# Strain_Gauge_Amplifier.net
KiCad netlist of a schematic drawn in EAGLE
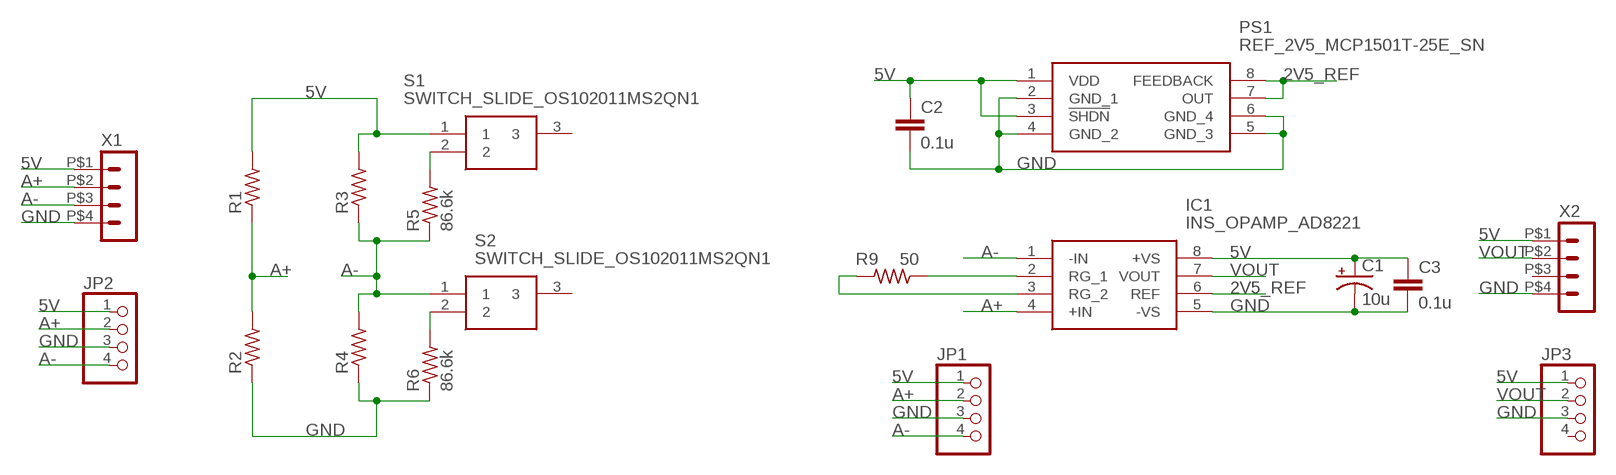
[diagram p0: schematic, sheet 1]

(export (version "E")
  (design (tool "Eeschema 10.0.6"))
  (components
    (comp (ref "C1")
      (value "10u")
      (footprint "eagle-import:E2-5")
      (libsource (lib "eagle-import") (part "CAP_THTE2-5"))
    )
    (comp (ref "C2")
      (value "0.1u")
      (footprint "eagle-import:C0603")
      (libsource (lib "eagle-import") (part "CAP_SMDC0603"))
    )
    (comp (ref "C3")
      (value "0.1u")
      (footprint "eagle-import:C0603")
      (libsource (lib "eagle-import") (part "CAP_SMDC0603"))
    )
    (comp (ref "IC1")
      (value "INS_OPAMP_AD8221")
      (footprint "eagle-import:SOP65P490X110-8N")
      (fields
        (field (name "ARROW_PART_NUMBER") "AD8221ARMZ-R7")
        (field (name "MOUSER_PART_NUMBER") "584-AD8221ARMZ-R7")
      )
      (libsource (lib "eagle-import") (part "INS_OPAMP_AD8221"))
    )
    (comp (ref "JP1")
      (value "PINHD-1X4")
      (footprint "eagle-import:1X04")
      (libsource (lib "eagle-import") (part "PINHD-1X4"))
    )
    (comp (ref "JP2")
      (value "PINHD-1X4")
      (footprint "eagle-import:1X04")
      (libsource (lib "eagle-import") (part "PINHD-1X4"))
    )
    (comp (ref "JP3")
      (value "PINHD-1X4")
      (footprint "eagle-import:1X04")
      (libsource (lib "eagle-import") (part "PINHD-1X4"))
    )
    (comp (ref "PS1")
      (value "REF_2V5_MCP1501T-25E_SN")
      (footprint "eagle-import:SOIC127P600X175-8N")
      (fields
        (field (name "ARROW_PART_NUMBER") "MCP1501T-25E/SN")
        (field (name "MOUSER_PART_NUMBER") "579-MCP1501T-25E/SN")
      )
      (libsource (lib "eagle-import") (part "REF_2V5_MCP1501T-25E_SN"))
    )
    (comp (ref "R1")
      (value "RES_SMDR1206")
      (footprint "eagle-import:R1206")
      (libsource (lib "eagle-import") (part "RES_SMDR1206"))
    )
    (comp (ref "R2")
      (value "RES_SMDR1206")
      (footprint "eagle-import:R1206")
      (libsource (lib "eagle-import") (part "RES_SMDR1206"))
    )
    (comp (ref "R3")
      (value "RES_SMDR1206")
      (footprint "eagle-import:R1206")
      (libsource (lib "eagle-import") (part "RES_SMDR1206"))
    )
    (comp (ref "R4")
      (value "RES_SMDR1206")
      (footprint "eagle-import:R1206")
      (libsource (lib "eagle-import") (part "RES_SMDR1206"))
    )
    (comp (ref "R5")
      (value "86.6k")
      (footprint "eagle-import:R0603")
      (libsource (lib "eagle-import") (part "RES_SMDR0603"))
    )
    (comp (ref "R6")
      (value "86.6k")
      (footprint "eagle-import:R0603")
      (libsource (lib "eagle-import") (part "RES_SMDR0603"))
    )
    (comp (ref "R9")
      (value "50")
      (footprint "eagle-import:R0603")
      (libsource (lib "eagle-import") (part "RES_SMDR0603"))
    )
    (comp (ref "S1")
      (value "SWITCH_SLIDE_OS102011MS2QN1")
      (footprint "eagle-import:OS102011MA1QN1")
      (fields
        (field (name "ARROW_PART_NUMBER") "OS102011MS2QN1")
        (field (name "MOUSER_PART_NUMBER") "611-OS102011MS2QN1")
      )
      (libsource (lib "eagle-import") (part "SWITCH_SLIDE_OS102011MS2QN1"))
    )
    (comp (ref "S2")
      (value "SWITCH_SLIDE_OS102011MS2QN1")
      (footprint "eagle-import:OS102011MA1QN1")
      (fields
        (field (name "ARROW_PART_NUMBER") "OS102011MS2QN1")
        (field (name "MOUSER_PART_NUMBER") "611-OS102011MS2QN1")
      )
      (libsource (lib "eagle-import") (part "SWITCH_SLIDE_OS102011MS2QN1"))
    )
    (comp (ref "X1")
      (value "HEADER_POS4_43045-0401")
      (footprint "eagle-import:43045-0400")
      (libsource (lib "eagle-import") (part "HEADER_POS4_?43045-0401"))
    )
    (comp (ref "X2")
      (value "HEADER_POS4_43045-0401")
      (footprint "eagle-import:43045-0400")
      (libsource (lib "eagle-import") (part "HEADER_POS4_?43045-0401"))
    )
  )
  (nets
    (net (code "1") (name "/2V5_REF") (class "Default")
      (node (ref "IC1") (pin "6") (pinfunction "REF_6") (pintype "bidirectional"))
      (node (ref "PS1") (pin "7") (pinfunction "OUT_7") (pintype "bidirectional"))
      (node (ref "PS1") (pin "8") (pinfunction "FEEDBACK_8") (pintype "bidirectional"))
    )
    (net (code "2") (name "/5V") (class "Default")
      (node (ref "C1") (pin "+") (pinfunction "+_+") (pintype "passive"))
      (node (ref "C2") (pin "1") (pinfunction "1_1") (pintype "passive"))
      (node (ref "C3") (pin "1") (pinfunction "1_1") (pintype "passive"))
      (node (ref "IC1") (pin "8") (pinfunction "+VS_8") (pintype "bidirectional"))
      (node (ref "JP1") (pin "1") (pinfunction "1_1") (pintype "passive"))
      (node (ref "JP2") (pin "1") (pinfunction "1_1") (pintype "passive"))
      (node (ref "JP3") (pin "1") (pinfunction "1_1") (pintype "passive"))
      (node (ref "PS1") (pin "1") (pinfunction "VDD_1") (pintype "bidirectional"))
      (node (ref "PS1") (pin "3") (pinfunction "~{SHDN}_3") (pintype "bidirectional"))
      (node (ref "R1") (pin "2") (pinfunction "2_2") (pintype "passive"))
      (node (ref "R3") (pin "2") (pinfunction "2_2") (pintype "passive"))
      (node (ref "S1") (pin "1") (pinfunction "1_1") (pintype "bidirectional"))
      (node (ref "X1") (pin "P$1") (pinfunction "1_P$1") (pintype "passive"))
      (node (ref "X2") (pin "P$1") (pinfunction "1_P$1") (pintype "passive"))
    )
    (net (code "3") (name "/A+") (class "Default")
      (node (ref "IC1") (pin "4") (pinfunction "+IN_4") (pintype "bidirectional"))
      (node (ref "JP1") (pin "2") (pinfunction "2_2") (pintype "passive"))
      (node (ref "JP2") (pin "2") (pinfunction "2_2") (pintype "passive"))
      (node (ref "R1") (pin "1") (pinfunction "1_1") (pintype "passive"))
      (node (ref "R2") (pin "2") (pinfunction "2_2") (pintype "passive"))
      (node (ref "X1") (pin "P$2") (pinfunction "2_P$2") (pintype "passive"))
    )
    (net (code "4") (name "/A-") (class "Default")
      (node (ref "IC1") (pin "1") (pinfunction "-IN_1") (pintype "bidirectional"))
      (node (ref "JP1") (pin "4") (pinfunction "4_4") (pintype "passive"))
      (node (ref "JP2") (pin "4") (pinfunction "4_4") (pintype "passive"))
      (node (ref "R3") (pin "1") (pinfunction "1_1") (pintype "passive"))
      (node (ref "R4") (pin "2") (pinfunction "2_2") (pintype "passive"))
      (node (ref "R5") (pin "1") (pinfunction "1_1") (pintype "passive"))
      (node (ref "S2") (pin "1") (pinfunction "1_1") (pintype "bidirectional"))
      (node (ref "X1") (pin "P$3") (pinfunction "3_P$3") (pintype "passive"))
    )
    (net (code "5") (name "/GND") (class "Default")
      (node (ref "C1") (pin "-") (pinfunction "-_-") (pintype "passive"))
      (node (ref "C2") (pin "2") (pinfunction "2_2") (pintype "passive"))
      (node (ref "C3") (pin "2") (pinfunction "2_2") (pintype "passive"))
      (node (ref "IC1") (pin "5") (pinfunction "-VS_5") (pintype "bidirectional"))
      (node (ref "JP1") (pin "3") (pinfunction "3_3") (pintype "passive"))
      (node (ref "JP2") (pin "3") (pinfunction "3_3") (pintype "passive"))
      (node (ref "JP3") (pin "3") (pinfunction "3_3") (pintype "passive"))
      (node (ref "PS1") (pin "2") (pinfunction "GND_1_2") (pintype "bidirectional"))
      (node (ref "PS1") (pin "4") (pinfunction "GND_2_4") (pintype "bidirectional"))
      (node (ref "PS1") (pin "5") (pinfunction "GND_3_5") (pintype "bidirectional"))
      (node (ref "PS1") (pin "6") (pinfunction "GND_4_6") (pintype "bidirectional"))
      (node (ref "R2") (pin "1") (pinfunction "1_1") (pintype "passive"))
      (node (ref "R4") (pin "1") (pinfunction "1_1") (pintype "passive"))
      (node (ref "R6") (pin "1") (pinfunction "1_1") (pintype "passive"))
      (node (ref "X1") (pin "P$4") (pinfunction "4_P$4") (pintype "passive"))
      (node (ref "X2") (pin "P$4") (pinfunction "4_P$4") (pintype "passive"))
    )
    (net (code "6") (name "/VOUT") (class "Default")
      (node (ref "IC1") (pin "7") (pinfunction "VOUT_7") (pintype "bidirectional"))
      (node (ref "JP3") (pin "2") (pinfunction "2_2") (pintype "passive"))
      (node (ref "X2") (pin "P$2") (pinfunction "2_P$2") (pintype "passive"))
    )
    (net (code "7") (name "Net-(IC1-RG_1)") (class "Default")
      (node (ref "IC1") (pin "2") (pinfunction "RG_1_2") (pintype "bidirectional"))
      (node (ref "R9") (pin "1") (pinfunction "1_1") (pintype "passive"))
    )
    (net (code "8") (name "Net-(IC1-RG_2)") (class "Default")
      (node (ref "IC1") (pin "3") (pinfunction "RG_2_3") (pintype "bidirectional"))
      (node (ref "R9") (pin "2") (pinfunction "2_2") (pintype "passive"))
    )
    (net (code "9") (name "Net-(R5-Pad2)") (class "Default")
      (node (ref "R5") (pin "2") (pinfunction "2_2") (pintype "passive"))
      (node (ref "S1") (pin "2") (pinfunction "2_2") (pintype "bidirectional"))
    )
    (net (code "10") (name "Net-(R6-Pad2)") (class "Default")
      (node (ref "R6") (pin "2") (pinfunction "2_2") (pintype "passive"))
      (node (ref "S2") (pin "2") (pinfunction "2_2") (pintype "bidirectional"))
    )
    (net (code "11") (name "unconnected-(JP3-Pad4)") (class "Default")
      (node (ref "JP3") (pin "4") (pinfunction "4_4") (pintype "passive"))
    )
    (net (code "12") (name "unconnected-(S1-Pad3)") (class "Default")
      (node (ref "S1") (pin "3") (pinfunction "3_3") (pintype "bidirectional"))
    )
    (net (code "13") (name "unconnected-(S2-Pad3)") (class "Default")
      (node (ref "S2") (pin "3") (pinfunction "3_3") (pintype "bidirectional"))
    )
    (net (code "14") (name "unconnected-(X2-3-PadP$3)") (class "Default")
      (node (ref "X2") (pin "P$3") (pinfunction "3_P$3") (pintype "passive"))
    )
  )
)
